# DATALOGGER_POWER_V1.net
KiCad netlist of a schematic drawn in EAGLE
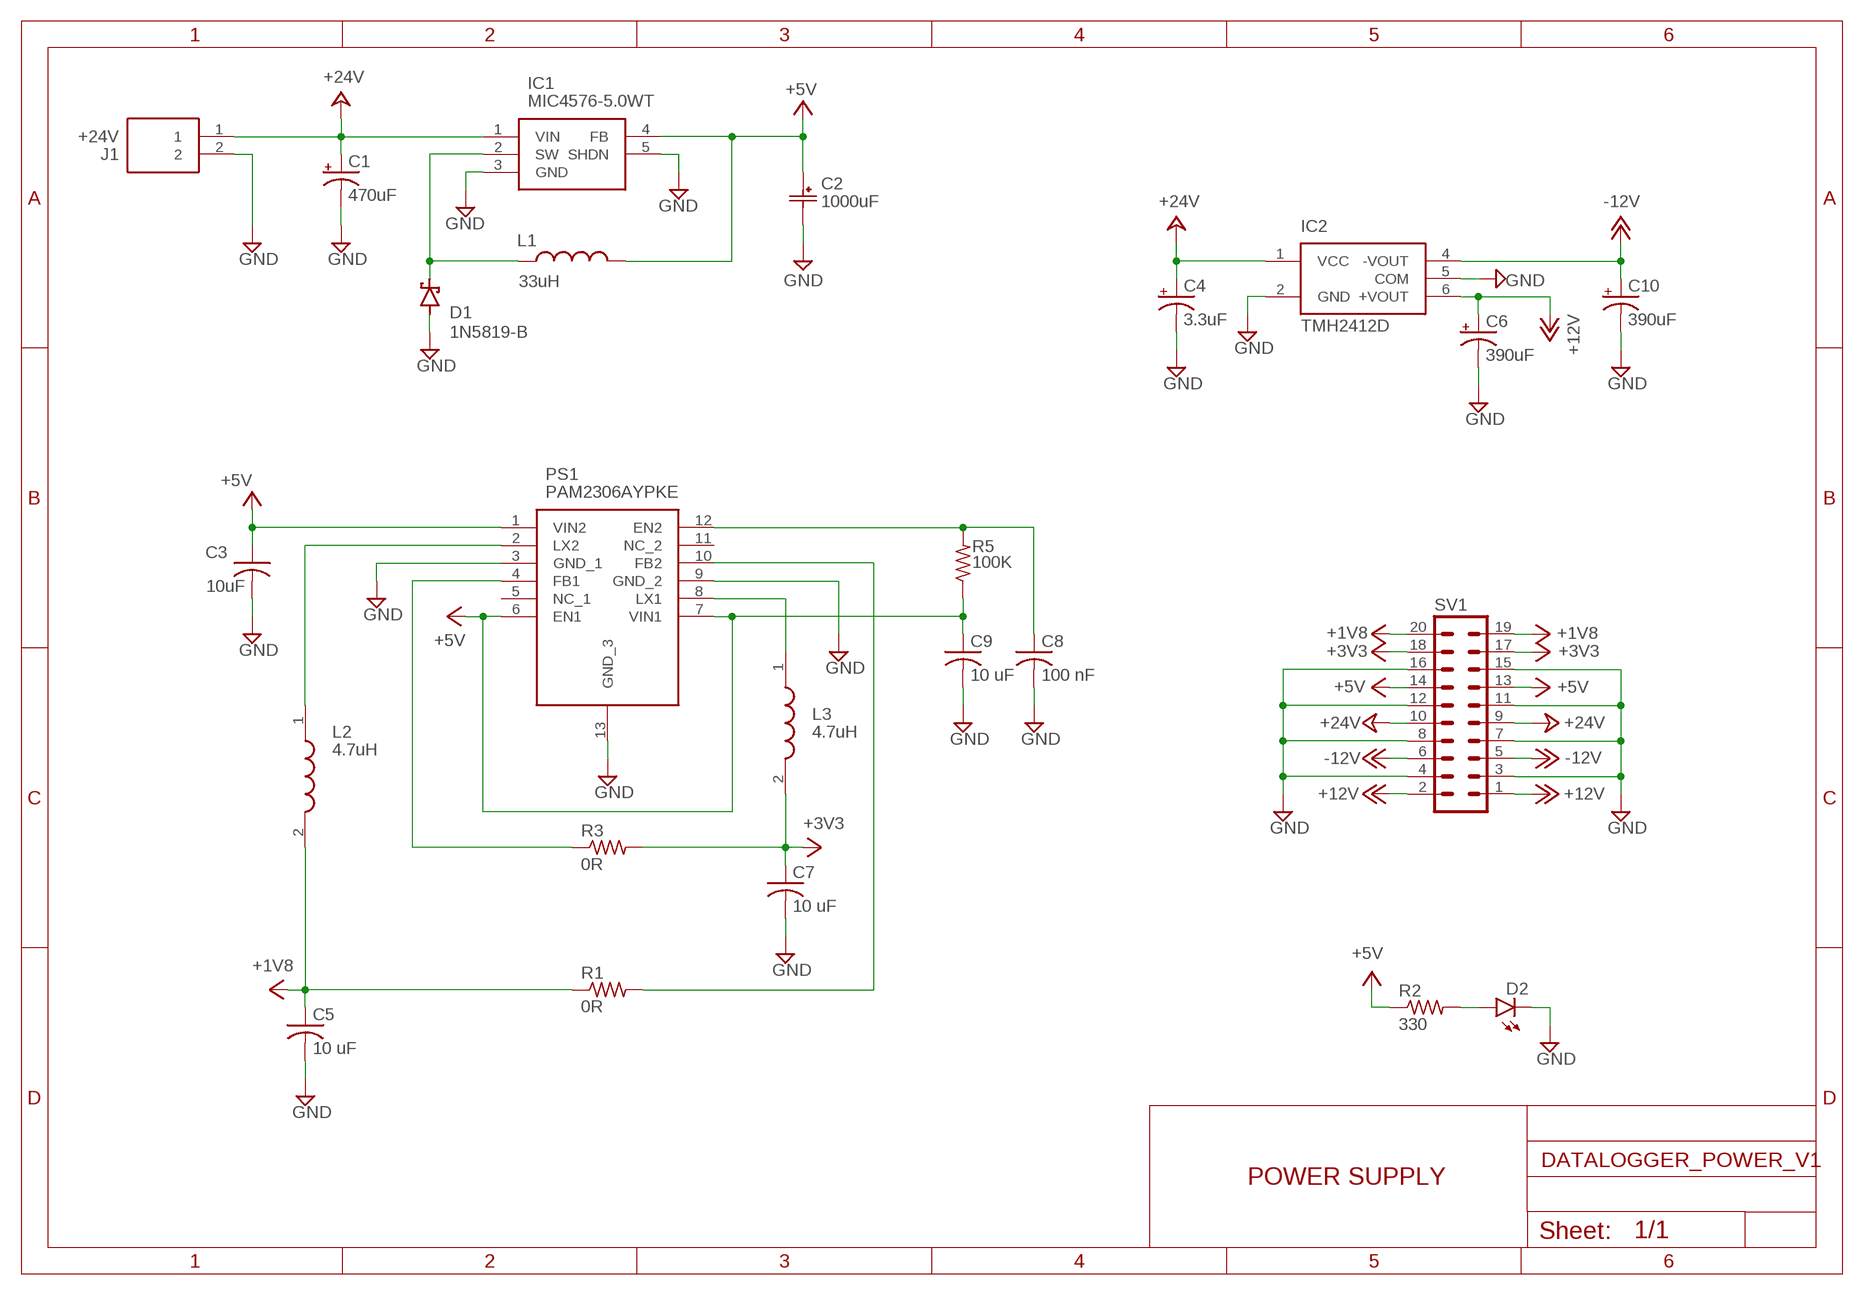
[diagram p0: schematic, sheet 1]

(export (version "E")
  (design (tool "Eeschema 10.0.6"))
  (components
    (comp (ref "C1")
      (value "470uF")
      (footprint "eagle-import:E5-13")
      (libsource (lib "eagle-import") (part "CPOL-USE5-13"))
    )
    (comp (ref "C2")
      (value "1000uF")
      (footprint "eagle-import:CAP_UCD_16X16P5_NCH")
      (fields
        (field (name "MANUFACTURER_PART_NUMBER") "UCZ1V102MNQ1MS")
        (field (name "COPYRIGHT") "Copyright (C) 2018 Accelerated Designs. All rights reserved")
      )
      (libsource (lib "eagle-import") (part "UCZ1V102MNQ1MS"))
    )
    (comp (ref "C3")
      (value "10uF")
      (footprint "eagle-import:C1206")
      (libsource (lib "eagle-import") (part "C-USC1206"))
    )
    (comp (ref "C4")
      (value "3.3uF")
      (footprint "eagle-import:E2-4")
      (libsource (lib "eagle-import") (part "CPOL-USE2-4"))
    )
    (comp (ref "C5")
      (value "10 uF")
      (footprint "eagle-import:C1206")
      (libsource (lib "eagle-import") (part "C-USC1206"))
    )
    (comp (ref "C6")
      (value "390uF")
      (footprint "eagle-import:E2-4")
      (libsource (lib "eagle-import") (part "CPOL-USE2-4"))
    )
    (comp (ref "C7")
      (value "10 uF")
      (footprint "eagle-import:C1206")
      (libsource (lib "eagle-import") (part "C-USC1206"))
    )
    (comp (ref "C8")
      (value "100 nF")
      (footprint "eagle-import:C1206")
      (libsource (lib "eagle-import") (part "C-USC1206"))
    )
    (comp (ref "C9")
      (value "10 uF")
      (footprint "eagle-import:C1206")
      (libsource (lib "eagle-import") (part "C-USC1206"))
    )
    (comp (ref "C10")
      (value "390uF")
      (footprint "eagle-import:E2-4")
      (libsource (lib "eagle-import") (part "CPOL-USE2-4"))
    )
    (comp (ref "D1")
      (value "1N5819-B")
      (footprint "eagle-import:DO41-7.6")
      (libsource (lib "eagle-import") (part "1N5819-B"))
    )
    (comp (ref "D2")
      (value "LEDCHIPLED_1206")
      (footprint "eagle-import:CHIPLED_1206")
      (libsource (lib "eagle-import") (part "LEDCHIPLED_1206"))
    )
    (comp (ref "IC1")
      (value "MIC4576-5.0WT")
      (footprint "eagle-import:TO170P470X1016X1600-5P")
      (fields (field (name "MOUSER_PART_NUMBER") "998-MIC4576-5.0WT"))
      (libsource (lib "eagle-import") (part "MIC4576-5.0WT"))
    )
    (comp (ref "IC2")
      (value "TMH2412D")
      (footprint "eagle-import:TMH2412D")
      (libsource (lib "eagle-import") (part "TMH2412D"))
    )
    (comp (ref "J1")
      (value "+24V")
      (footprint "eagle-import:SHDR2W110P0X500_1X2_1000X1120X")
      (fields
        (field (name "MANUFACTURER_PART_NUMBER") "1711026")
        (field (name "MOUSER_PART_NUMBER") "651-1711026")
      )
      (libsource (lib "eagle-import") (part "1711026"))
    )
    (comp (ref "L1")
      (value "33uH")
      (footprint "eagle-import:HCMA1707-330-R")
      (libsource (lib "eagle-import") (part "HCMA1707-330-R"))
    )
    (comp (ref "L2")
      (value "4.7uH")
      (footprint "eagle-import:SRN4018")
      (fields
        (field (name "MANUFACTURER_PART_NUMBER") "SRN4018-4R7M")
        (field (name "MOUSER_PART_NUMBER") "652-SRN4018-4R7M")
      )
      (libsource (lib "eagle-import") (part "SRN4018-4R7M"))
    )
    (comp (ref "L3")
      (value "4.7uH")
      (footprint "eagle-import:SRN4018")
      (fields
        (field (name "MANUFACTURER_PART_NUMBER") "SRN4018-4R7M")
        (field (name "MOUSER_PART_NUMBER") "652-SRN4018-4R7M")
      )
      (libsource (lib "eagle-import") (part "SRN4018-4R7M"))
    )
    (comp (ref "PS1")
      (value "PAM2306AYPKE")
      (footprint "eagle-import:SON45P300X300X80-13N")
      (fields
        (field (name "MOUSER_PART_NUMBER") "621-PAM2306AYPKE")
        (field (name "RS_PART_NUMBER") "9210751P")
      )
      (libsource (lib "eagle-import") (part "PAM2306AYPKE"))
    )
    (comp (ref "R1")
      (value "0R")
      (footprint "eagle-import:R1206")
      (libsource (lib "eagle-import") (part "R-US_R1206"))
    )
    (comp (ref "R2")
      (value "330")
      (footprint "eagle-import:R1206")
      (libsource (lib "eagle-import") (part "R-US_R1206"))
    )
    (comp (ref "R3")
      (value "0R")
      (footprint "eagle-import:R1206")
      (libsource (lib "eagle-import") (part "R-US_R1206"))
    )
    (comp (ref "R5")
      (value "100K")
      (footprint "eagle-import:R1206")
      (libsource (lib "eagle-import") (part "R-US_R1206"))
    )
    (comp (ref "SV1")
      (value "MA10-2")
      (footprint "eagle-import:MA10-2")
      (libsource (lib "eagle-import") (part "MA10-2"))
    )
  )
  (nets
    (net (code "1") (name "+1V8") (class "Default")
      (node (ref "C5") (pin "1") (pinfunction "1_1") (pintype "passive"))
      (node (ref "L2") (pin "2") (pinfunction "2_2") (pintype "bidirectional"))
      (node (ref "R1") (pin "1") (pinfunction "1_1") (pintype "passive"))
      (node (ref "SV1") (pin "19") (pinfunction "19_19") (pintype "passive"))
      (node (ref "SV1") (pin "20") (pinfunction "20_20") (pintype "passive"))
    )
    (net (code "2") (name "+3V3") (class "Default")
      (node (ref "C7") (pin "1") (pinfunction "1_1") (pintype "passive"))
      (node (ref "L3") (pin "2") (pinfunction "2_2") (pintype "bidirectional"))
      (node (ref "R3") (pin "2") (pinfunction "2_2") (pintype "passive"))
      (node (ref "SV1") (pin "17") (pinfunction "17_17") (pintype "passive"))
      (node (ref "SV1") (pin "18") (pinfunction "18_18") (pintype "passive"))
    )
    (net (code "3") (name "+5V") (class "Default")
      (node (ref "C2") (pin "1") (pinfunction "1_1") (pintype "passive"))
      (node (ref "C3") (pin "1") (pinfunction "1_1") (pintype "passive"))
      (node (ref "C9") (pin "1") (pinfunction "1_1") (pintype "passive"))
      (node (ref "IC1") (pin "4") (pinfunction "FB_4") (pintype "bidirectional"))
      (node (ref "L1") (pin "2") (pinfunction "2_2") (pintype "passive"))
      (node (ref "PS1") (pin "1") (pinfunction "VIN2_1") (pintype "power_in"))
      (node (ref "PS1") (pin "6") (pinfunction "EN1_6") (pintype "input"))
      (node (ref "PS1") (pin "7") (pinfunction "VIN1_7") (pintype "power_in"))
      (node (ref "R2") (pin "1") (pinfunction "1_1") (pintype "passive"))
      (node (ref "R5") (pin "1") (pinfunction "1_1") (pintype "passive"))
      (node (ref "SV1") (pin "13") (pinfunction "13_13") (pintype "passive"))
      (node (ref "SV1") (pin "14") (pinfunction "14_14") (pintype "passive"))
    )
    (net (code "4") (name "+12V") (class "Default")
      (node (ref "C6") (pin "+") (pinfunction "+_+") (pintype "passive"))
      (node (ref "IC2") (pin "6") (pinfunction "+VOUT_6") (pintype "bidirectional"))
      (node (ref "SV1") (pin "1") (pinfunction "1_1") (pintype "passive"))
      (node (ref "SV1") (pin "2") (pinfunction "2_2") (pintype "passive"))
    )
    (net (code "5") (name "+24V") (class "Default")
      (node (ref "C1") (pin "+") (pinfunction "+_+") (pintype "passive"))
      (node (ref "C4") (pin "+") (pinfunction "+_+") (pintype "passive"))
      (node (ref "IC1") (pin "1") (pinfunction "VIN_1") (pintype "bidirectional"))
      (node (ref "IC2") (pin "1") (pinfunction "VCC_1") (pintype "bidirectional"))
      (node (ref "J1") (pin "1") (pinfunction "1_1") (pintype "bidirectional"))
      (node (ref "SV1") (pin "10") (pinfunction "10_10") (pintype "passive"))
      (node (ref "SV1") (pin "9") (pinfunction "9_9") (pintype "passive"))
    )
    (net (code "6") (name "-12V") (class "Default")
      (node (ref "C10") (pin "+") (pinfunction "+_+") (pintype "passive"))
      (node (ref "IC2") (pin "4") (pinfunction "-VOUT_4") (pintype "bidirectional"))
      (node (ref "SV1") (pin "5") (pinfunction "5_5") (pintype "passive"))
      (node (ref "SV1") (pin "6") (pinfunction "6_6") (pintype "passive"))
    )
    (net (code "7") (name "GND") (class "Default")
      (node (ref "C1") (pin "-") (pinfunction "-_-") (pintype "passive"))
      (node (ref "C10") (pin "-") (pinfunction "-_-") (pintype "passive"))
      (node (ref "C2") (pin "2") (pinfunction "2_2") (pintype "passive"))
      (node (ref "C3") (pin "2") (pinfunction "2_2") (pintype "passive"))
      (node (ref "C4") (pin "-") (pinfunction "-_-") (pintype "passive"))
      (node (ref "C5") (pin "2") (pinfunction "2_2") (pintype "passive"))
      (node (ref "C6") (pin "-") (pinfunction "-_-") (pintype "passive"))
      (node (ref "C7") (pin "2") (pinfunction "2_2") (pintype "passive"))
      (node (ref "C8") (pin "2") (pinfunction "2_2") (pintype "passive"))
      (node (ref "C9") (pin "2") (pinfunction "2_2") (pintype "passive"))
      (node (ref "D1") (pin "A") (pinfunction "A_A") (pintype "passive"))
      (node (ref "D2") (pin "C") (pinfunction "C_C") (pintype "passive"))
      (node (ref "IC1") (pin "3") (pinfunction "GND_3") (pintype "bidirectional"))
      (node (ref "IC1") (pin "5") (pinfunction "SHDN_5") (pintype "bidirectional"))
      (node (ref "IC2") (pin "2") (pinfunction "GND_2") (pintype "bidirectional"))
      (node (ref "IC2") (pin "5") (pinfunction "COM_5") (pintype "bidirectional"))
      (node (ref "J1") (pin "2") (pinfunction "2_2") (pintype "bidirectional"))
      (node (ref "PS1") (pin "13") (pinfunction "GND_3_13") (pintype "power_in"))
      (node (ref "PS1") (pin "3") (pinfunction "GND_1_3") (pintype "power_in"))
      (node (ref "PS1") (pin "9") (pinfunction "GND_2_9") (pintype "power_in"))
      (node (ref "SV1") (pin "11") (pinfunction "11_11") (pintype "passive"))
      (node (ref "SV1") (pin "12") (pinfunction "12_12") (pintype "passive"))
      (node (ref "SV1") (pin "15") (pinfunction "15_15") (pintype "passive"))
      (node (ref "SV1") (pin "16") (pinfunction "16_16") (pintype "passive"))
      (node (ref "SV1") (pin "3") (pinfunction "3_3") (pintype "passive"))
      (node (ref "SV1") (pin "4") (pinfunction "4_4") (pintype "passive"))
      (node (ref "SV1") (pin "7") (pinfunction "7_7") (pintype "passive"))
      (node (ref "SV1") (pin "8") (pinfunction "8_8") (pintype "passive"))
    )
    (net (code "8") (name "Net-(D2-PadA)") (class "Default")
      (node (ref "D2") (pin "A") (pinfunction "A_A") (pintype "passive"))
      (node (ref "R2") (pin "2") (pinfunction "2_2") (pintype "passive"))
    )
    (net (code "9") (name "Net-(IC1-SW)") (class "Default")
      (node (ref "D1") (pin "C") (pinfunction "C_C") (pintype "passive"))
      (node (ref "IC1") (pin "2") (pinfunction "SW_2") (pintype "bidirectional"))
      (node (ref "L1") (pin "1") (pinfunction "1_1") (pintype "passive"))
    )
    (net (code "10") (name "Net-(PS1-EN2)") (class "Default")
      (node (ref "C8") (pin "1") (pinfunction "1_1") (pintype "passive"))
      (node (ref "PS1") (pin "12") (pinfunction "EN2_12") (pintype "input"))
      (node (ref "R5") (pin "2") (pinfunction "2_2") (pintype "passive"))
    )
    (net (code "11") (name "Net-(PS1-FB1)") (class "Default")
      (node (ref "PS1") (pin "4") (pinfunction "FB1_4") (pintype "input"))
      (node (ref "R3") (pin "1") (pinfunction "1_1") (pintype "passive"))
    )
    (net (code "12") (name "Net-(PS1-FB2)") (class "Default")
      (node (ref "PS1") (pin "10") (pinfunction "FB2_10") (pintype "input"))
      (node (ref "R1") (pin "2") (pinfunction "2_2") (pintype "passive"))
    )
    (net (code "13") (name "Net-(PS1-LX1)") (class "Default")
      (node (ref "L3") (pin "1") (pinfunction "1_1") (pintype "bidirectional"))
      (node (ref "PS1") (pin "8") (pinfunction "LX1_8") (pintype "bidirectional"))
    )
    (net (code "14") (name "Net-(PS1-LX2)") (class "Default")
      (node (ref "L2") (pin "1") (pinfunction "1_1") (pintype "bidirectional"))
      (node (ref "PS1") (pin "2") (pinfunction "LX2_2") (pintype "bidirectional"))
    )
    (net (code "15") (name "unconnected-(PS1-NC_1-Pad5)") (class "Default")
      (node (ref "PS1") (pin "5") (pinfunction "NC_1_5") (pintype "bidirectional"))
    )
    (net (code "16") (name "unconnected-(PS1-NC_2-Pad11)") (class "Default")
      (node (ref "PS1") (pin "11") (pinfunction "NC_2_11") (pintype "bidirectional"))
    )
  )
)
